# PLC_V1_0.net
KiCad netlist of a schematic drawn in Altium Designer
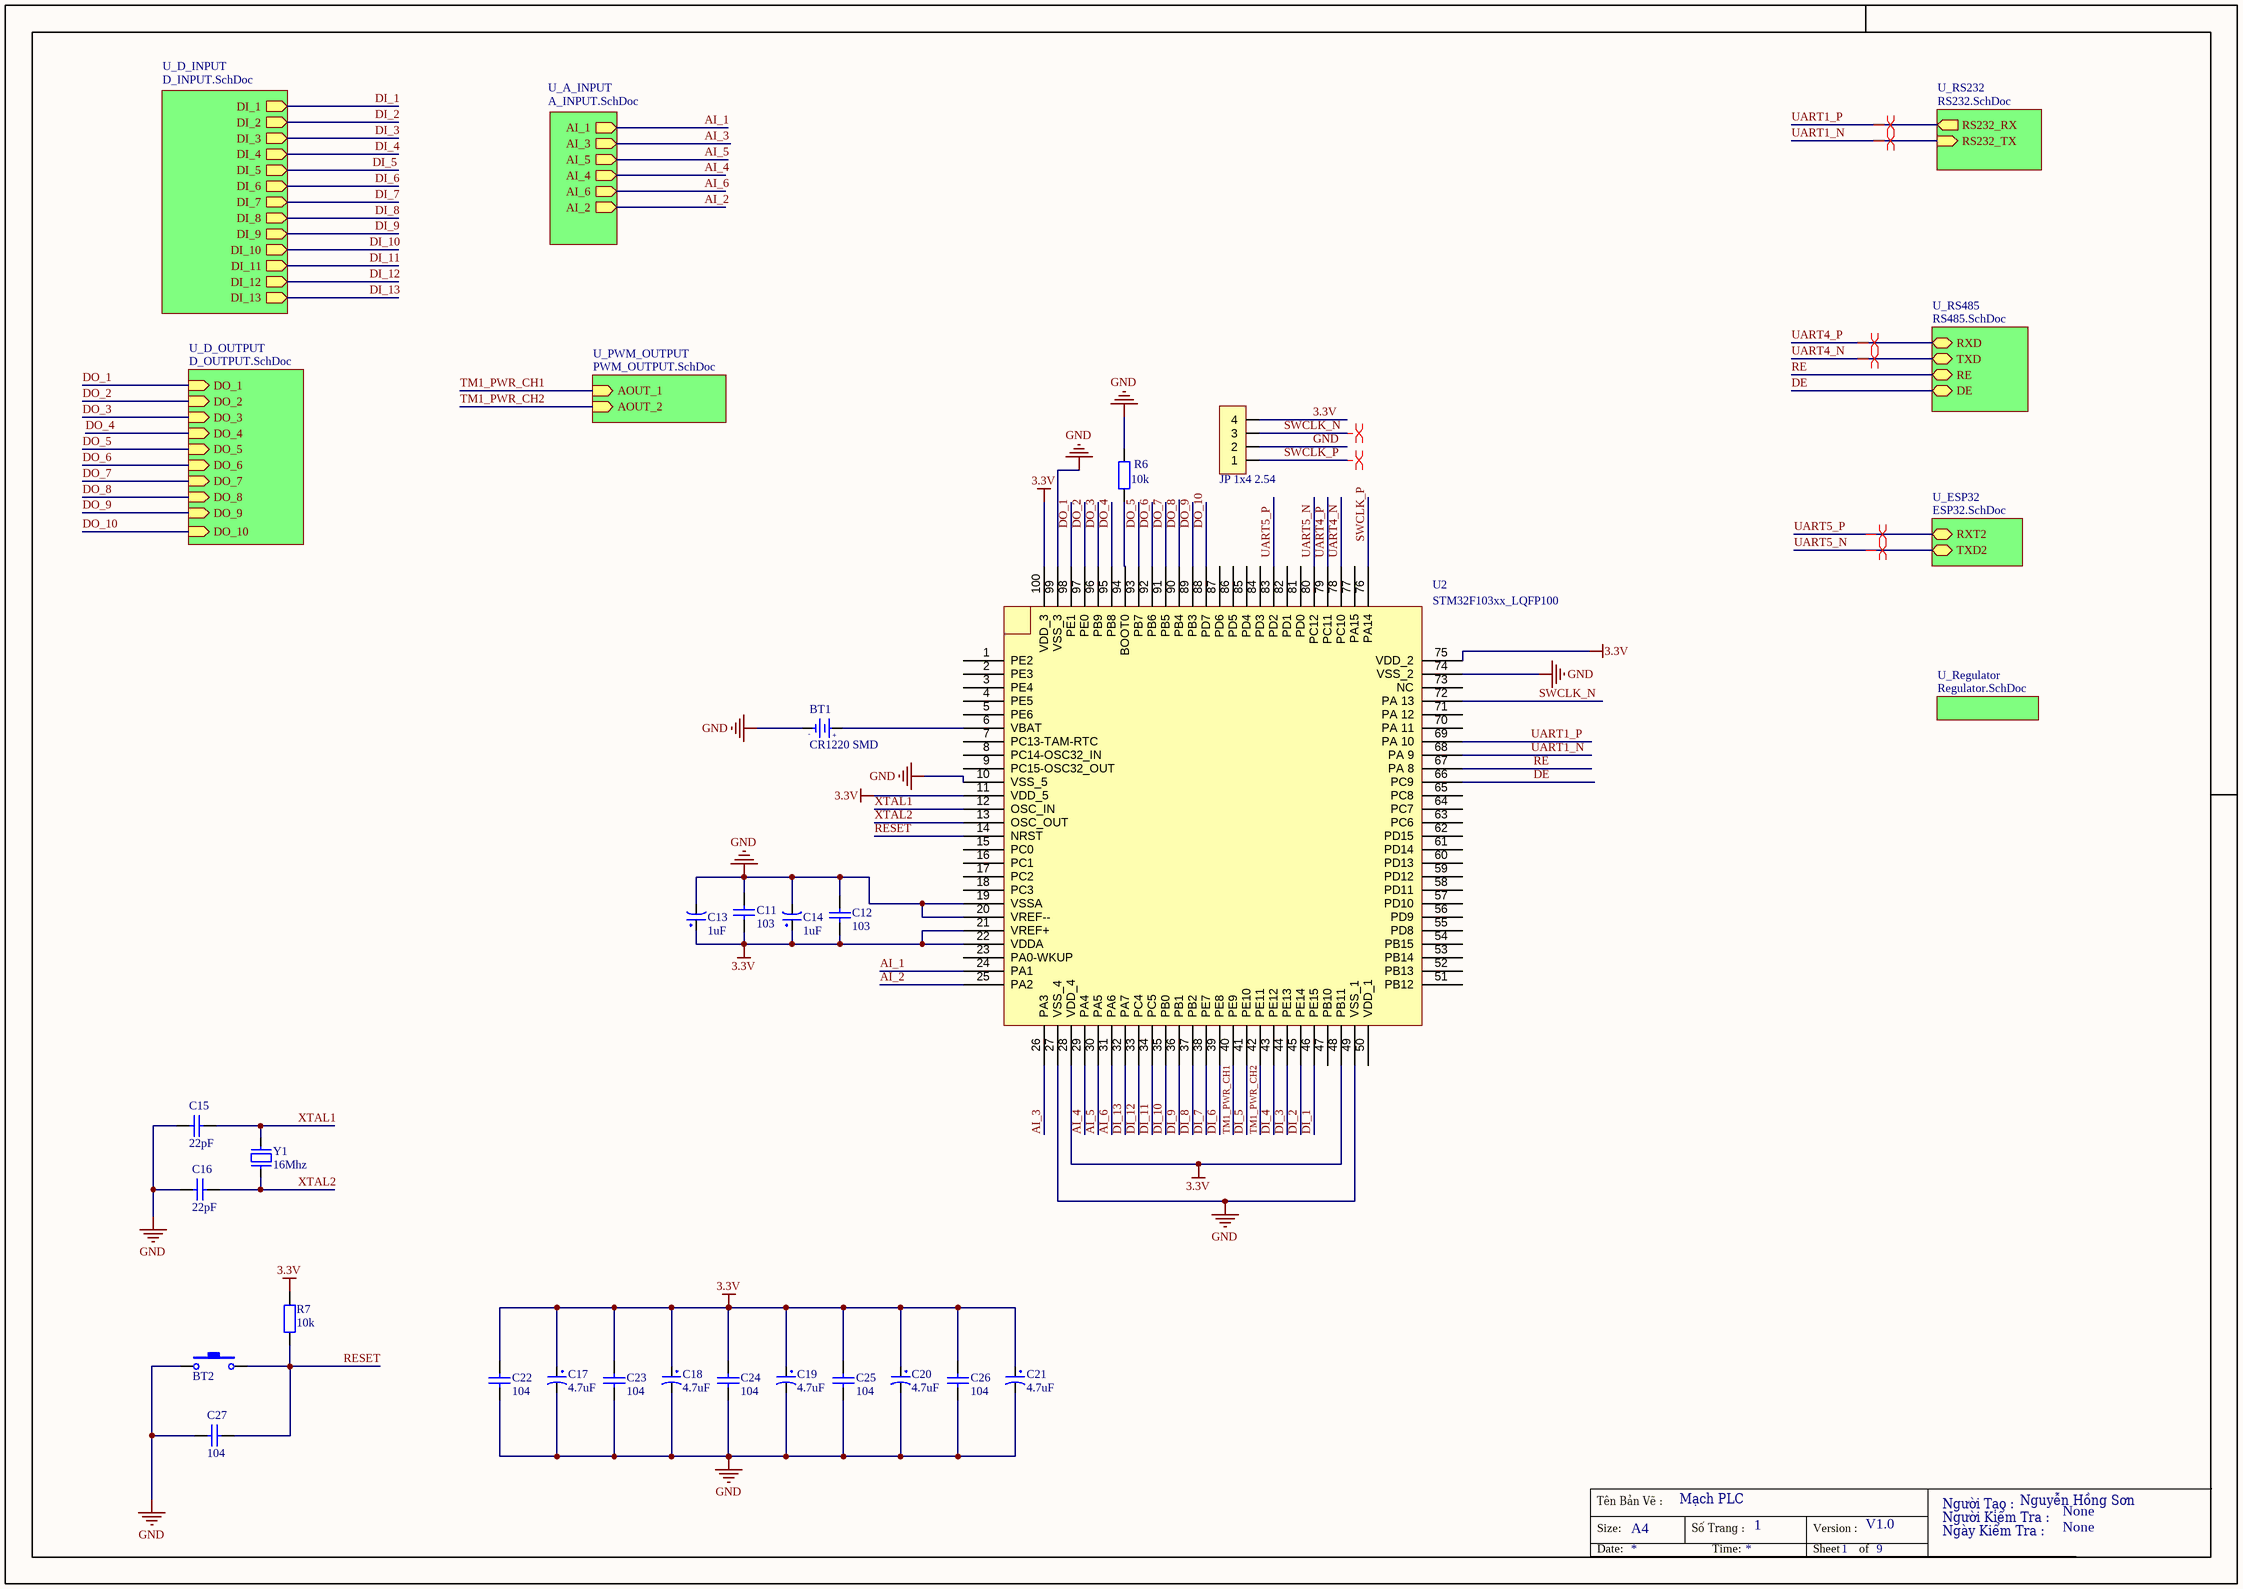
[diagram p0: PLC_V1.0.SchDoc]

(export (version "E")
  (design (tool "Eeschema 10.0.6"))
  (components
    (comp (ref "BT1")
      (value "CR1220 SMD")
      (footprint "DE PIN CR1220")
      (libsource (lib "Altium_Lib_by_KhueNguyenCreator") (part "De pin CR1220 SMD"))
    )
    (comp (ref "BT2")
      (value "Nut Nhan 2 Chan SMD 3x6x2.5")
      (footprint "Nut Nhan 2 Chan SMD 3x6x2.5")
      (libsource (lib "Altium_Lib_by_KhueNguyenCreator") (part "Nut Nhan 2 Chan SMD 3x6x2.5"))
    )
    (comp (ref "C11")
      (value "103")
      (footprint "tu 0603")
      (description "Dán")
      (libsource (lib "Altium_Lib_by_KhueNguyenCreator") (part "Tu 0603 103 50V 10%"))
    )
    (comp (ref "C12")
      (value "103")
      (footprint "tu 0603")
      (description "Dán")
      (libsource (lib "Altium_Lib_by_KhueNguyenCreator") (part "Tu 0603 103 50V 10%"))
    )
    (comp (ref "C13")
      (value "1uF")
      (footprint "tu tantalum smd3216")
      (description "Dán")
      (libsource (lib "Altium_Lib_by_KhueNguyenCreator") (part "Tu tantalum 1uF 25V SMD3216"))
    )
    (comp (ref "C14")
      (value "1uF")
      (footprint "tu tantalum smd3216")
      (description "Dán")
      (libsource (lib "Altium_Lib_by_KhueNguyenCreator") (part "Tu tantalum 1uF 25V SMD3216"))
    )
    (comp (ref "C15")
      (value "22pF")
      (footprint "tu 0805")
      (description "Dán")
      (libsource (lib "Altium_Lib_by_KhueNguyenCreator") (part "Tu 0805 22pF 50V 10%"))
    )
    (comp (ref "C16")
      (value "22pF")
      (footprint "tu 0805")
      (description "Dán")
      (libsource (lib "Altium_Lib_by_KhueNguyenCreator") (part "Tu 0805 22pF 50V 10%"))
    )
    (comp (ref "C17")
      (value "4.7uF")
      (footprint "tu tantalum smd6032")
      (description "Dán")
      (libsource (lib "Altium_Lib_by_KhueNguyenCreator") (part "Tu tantalum 4.7uF 35V SMD6032"))
    )
    (comp (ref "C18")
      (value "4.7uF")
      (footprint "tu tantalum smd6032")
      (description "Dán")
      (libsource (lib "Altium_Lib_by_KhueNguyenCreator") (part "Tu tantalum 4.7uF 35V SMD6032"))
    )
    (comp (ref "C19")
      (value "4.7uF")
      (footprint "tu tantalum smd6032")
      (description "Dán")
      (libsource (lib "Altium_Lib_by_KhueNguyenCreator") (part "Tu tantalum 4.7uF 35V SMD6032"))
    )
    (comp (ref "C20")
      (value "4.7uF")
      (footprint "tu tantalum smd6032")
      (description "Dán")
      (libsource (lib "Altium_Lib_by_KhueNguyenCreator") (part "Tu tantalum 4.7uF 35V SMD6032"))
    )
    (comp (ref "C21")
      (value "4.7uF")
      (footprint "tu tantalum smd6032")
      (description "Dán")
      (libsource (lib "Altium_Lib_by_KhueNguyenCreator") (part "Tu tantalum 4.7uF 35V SMD6032"))
    )
    (comp (ref "C22")
      (value "104")
      (footprint "tu 0805")
      (description "Dán 100nF")
      (libsource (lib "Altium_Lib_by_KhueNguyenCreator") (part "Tu 0805 104 50V 10%"))
    )
    (comp (ref "C23")
      (value "104")
      (footprint "tu 0805")
      (description "Dán 100nF")
      (libsource (lib "Altium_Lib_by_KhueNguyenCreator") (part "Tu 0805 104 50V 10%"))
    )
    (comp (ref "C24")
      (value "104")
      (footprint "tu 0805")
      (description "Dán 100nF")
      (libsource (lib "Altium_Lib_by_KhueNguyenCreator") (part "Tu 0805 104 50V 10%"))
    )
    (comp (ref "C25")
      (value "104")
      (footprint "tu 0805")
      (description "Dán 100nF")
      (libsource (lib "Altium_Lib_by_KhueNguyenCreator") (part "Tu 0805 104 50V 10%"))
    )
    (comp (ref "C26")
      (value "104")
      (footprint "tu 0805")
      (description "Dán 100nF")
      (libsource (lib "Altium_Lib_by_KhueNguyenCreator") (part "Tu 0805 104 50V 10%"))
    )
    (comp (ref "C27")
      (value "104")
      (footprint "tu 0805")
      (description "Dán")
      (libsource (lib "Altium_Lib_by_KhueNguyenCreator") (part "Tu 0805 104 50V 10%"))
    )
    (comp (ref "JP1")
      (value "JP 1x4 2.54")
      (footprint "JP 1x4 DT")
      (description "Cắm")
      (libsource (lib "Altium_Lib_by_KhueNguyenCreator") (part "JP 1x4 2.54 Duc Thang"))
    )
    (comp (ref "R6")
      (value "10k")
      (footprint "tro smd 0805")
      (description "Dán")
      (libsource (lib "Altium_Lib_by_KhueNguyenCreator") (part "Tro 0805 5% 10k"))
    )
    (comp (ref "R7")
      (value "10k")
      (footprint "tro smd 0805")
      (description "Dán")
      (libsource (lib "Altium_Lib_by_KhueNguyenCreator") (part "Tro 0805 5% 10k"))
    )
    (comp (ref "U2")
      (value "STM32F103xx_LQFP100")
      (footprint "STM32_LQFP100")
      (libsource (lib "Altium_Lib_by_KhueNguyenCreator") (part "STM32F103xx_LQFP100"))
    )
    (comp (ref "Y1")
      (value "16Mhz")
      (footprint "Thach Anh 2 chan SMD")
      (description "Crystal For all Crystal 2pin.")
      (libsource (lib "Altium_Lib_by_KhueNguyenCreator") (part "Thach Anh 2 chan SMD"))
    )
  )
  (nets
    (net (code "1") (name "/AI_1") (class "Default")
      (node (ref "U2") (pin "24") (pinfunction "PA1_24") (pintype "passive"))
    )
    (net (code "2") (name "/AI_2") (class "Default")
      (node (ref "U2") (pin "25") (pinfunction "PA2_25") (pintype "passive"))
    )
    (net (code "3") (name "/AI_3") (class "Default")
      (node (ref "U2") (pin "26") (pinfunction "PA3_26") (pintype "passive"))
    )
    (net (code "4") (name "/AI_4") (class "Default")
      (node (ref "U2") (pin "29") (pinfunction "PA4_29") (pintype "passive"))
    )
    (net (code "5") (name "/AI_5") (class "Default")
      (node (ref "U2") (pin "30") (pinfunction "PA5_30") (pintype "passive"))
    )
    (net (code "6") (name "/AI_6") (class "Default")
      (node (ref "U2") (pin "31") (pinfunction "PA6_31") (pintype "passive"))
    )
    (net (code "7") (name "/DE") (class "Default")
      (node (ref "U2") (pin "66") (pinfunction "PC9_66") (pintype "passive"))
    )
    (net (code "8") (name "/DI_1") (class "Default")
      (node (ref "U2") (pin "46") (pinfunction "PE15_46") (pintype "passive"))
    )
    (net (code "9") (name "/DI_2") (class "Default")
      (node (ref "U2") (pin "45") (pinfunction "PE14_45") (pintype "passive"))
    )
    (net (code "10") (name "/DI_3") (class "Default")
      (node (ref "U2") (pin "44") (pinfunction "PE13_44") (pintype "passive"))
    )
    (net (code "11") (name "/DI_4") (class "Default")
      (node (ref "U2") (pin "43") (pinfunction "PE12_43") (pintype "passive"))
    )
    (net (code "12") (name "/DI_5") (class "Default")
      (node (ref "U2") (pin "41") (pinfunction "PE10_41") (pintype "passive"))
    )
    (net (code "13") (name "/DI_6") (class "Default")
      (node (ref "U2") (pin "39") (pinfunction "PE8_39") (pintype "passive"))
    )
    (net (code "14") (name "/DI_7") (class "Default")
      (node (ref "U2") (pin "38") (pinfunction "PE7_38") (pintype "passive"))
    )
    (net (code "15") (name "/DI_8") (class "Default")
      (node (ref "U2") (pin "37") (pinfunction "PB2_37") (pintype "passive"))
    )
    (net (code "16") (name "/DI_9") (class "Default")
      (node (ref "U2") (pin "36") (pinfunction "PB1_36") (pintype "passive"))
    )
    (net (code "17") (name "/DI_10") (class "Default")
      (node (ref "U2") (pin "35") (pinfunction "PB0_35") (pintype "passive"))
    )
    (net (code "18") (name "/DI_11") (class "Default")
      (node (ref "U2") (pin "34") (pinfunction "PC5_34") (pintype "passive"))
    )
    (net (code "20") (name "/DI_12") (class "Default")
      (node (ref "U2") (pin "33") (pinfunction "PC4_33") (pintype "passive"))
    )
    (net (code "22") (name "/DI_13") (class "Default")
      (node (ref "U2") (pin "32") (pinfunction "PA7_32") (pintype "passive"))
    )
    (net (code "24") (name "/DO_1") (class "Default")
      (node (ref "U2") (pin "98") (pinfunction "PE1_98") (pintype "passive"))
    )
    (net (code "25") (name "/DO_2") (class "Default")
      (node (ref "U2") (pin "97") (pinfunction "PE0_97") (pintype "passive"))
    )
    (net (code "26") (name "/DO_3") (class "Default")
      (node (ref "U2") (pin "96") (pinfunction "PB9_96") (pintype "passive"))
    )
    (net (code "27") (name "/DO_4") (class "Default")
      (node (ref "U2") (pin "95") (pinfunction "PB8_95") (pintype "passive"))
    )
    (net (code "28") (name "/DO_5") (class "Default")
      (node (ref "U2") (pin "93") (pinfunction "PB7_93") (pintype "passive"))
    )
    (net (code "29") (name "/DO_6") (class "Default")
      (node (ref "U2") (pin "92") (pinfunction "PB6_92") (pintype "passive"))
    )
    (net (code "30") (name "/DO_7") (class "Default")
      (node (ref "U2") (pin "91") (pinfunction "PB5_91") (pintype "passive"))
    )
    (net (code "31") (name "/DO_8") (class "Default")
      (node (ref "U2") (pin "90") (pinfunction "PB4_90") (pintype "passive"))
    )
    (net (code "32") (name "/DO_9") (class "Default")
      (node (ref "U2") (pin "89") (pinfunction "PB3_89") (pintype "passive"))
    )
    (net (code "33") (name "/DO_10") (class "Default")
      (node (ref "U2") (pin "88") (pinfunction "PD7_88") (pintype "passive"))
    )
    (net (code "34") (name "/RE") (class "Default")
      (node (ref "U2") (pin "67") (pinfunction "PA_8_67") (pintype "passive"))
    )
    (net (code "35") (name "/RESET") (class "Default")
      (node (ref "BT2") (pin "2") (pinfunction "2_2") (pintype "passive"))
      (node (ref "C27") (pin "1") (pinfunction "1_1") (pintype "passive"))
      (node (ref "R7") (pin "2") (pinfunction "2_2") (pintype "passive"))
      (node (ref "U2") (pin "14") (pinfunction "NRST_14") (pintype "passive"))
    )
    (net (code "36") (name "/SWCLK_N") (class "Default")
      (node (ref "JP1") (pin "3") (pinfunction "3_3") (pintype "passive"))
      (node (ref "U2") (pin "72") (pinfunction "PA_13_72") (pintype "passive"))
    )
    (net (code "37") (name "/SWCLK_P") (class "Default")
      (node (ref "JP1") (pin "1") (pinfunction "1_1") (pintype "passive"))
      (node (ref "U2") (pin "76") (pinfunction "PA14_76") (pintype "passive"))
    )
    (net (code "38") (name "/TM1_PWR_CH1") (class "Default")
      (node (ref "U2") (pin "40") (pinfunction "PE9_40") (pintype "passive"))
    )
    (net (code "39") (name "/TM1_PWR_CH2") (class "Default")
      (node (ref "U2") (pin "42") (pinfunction "PE11_42") (pintype "passive"))
    )
    (net (code "40") (name "/UART1_N") (class "Default")
      (node (ref "U2") (pin "68") (pinfunction "PA_9_68") (pintype "passive"))
    )
    (net (code "41") (name "/UART1_P") (class "Default")
      (node (ref "U2") (pin "69") (pinfunction "PA_10_69") (pintype "passive"))
    )
    (net (code "42") (name "/UART4_N") (class "Default")
      (node (ref "U2") (pin "78") (pinfunction "PC10_78") (pintype "passive"))
    )
    (net (code "43") (name "/UART4_P") (class "Default")
      (node (ref "U2") (pin "79") (pinfunction "PC11_79") (pintype "passive"))
    )
    (net (code "44") (name "/UART5_N") (class "Default")
      (node (ref "U2") (pin "80") (pinfunction "PC12_80") (pintype "passive"))
    )
    (net (code "45") (name "/UART5_P") (class "Default")
      (node (ref "U2") (pin "83") (pinfunction "PD2_83") (pintype "passive"))
    )
    (net (code "46") (name "/XTAL1") (class "Default")
      (node (ref "C15") (pin "1") (pinfunction "1_1") (pintype "passive"))
      (node (ref "U2") (pin "12") (pinfunction "OSC_IN_12") (pintype "passive"))
      (node (ref "Y1") (pin "2") (pinfunction "2_2") (pintype "passive"))
    )
    (net (code "47") (name "/XTAL2") (class "Default")
      (node (ref "C16") (pin "1") (pinfunction "1_1") (pintype "passive"))
      (node (ref "U2") (pin "13") (pinfunction "OSC_OUT_13") (pintype "passive"))
      (node (ref "Y1") (pin "1") (pinfunction "1_1") (pintype "passive"))
    )
    (net (code "48") (name "3.3V") (class "Default")
      (node (ref "C11") (pin "1") (pinfunction "1_1") (pintype "passive"))
      (node (ref "C12") (pin "1") (pinfunction "1_1") (pintype "passive"))
      (node (ref "C13") (pin "1") (pinfunction "1_1") (pintype "passive"))
      (node (ref "C14") (pin "1") (pinfunction "1_1") (pintype "passive"))
      (node (ref "C17") (pin "1") (pinfunction "1_1") (pintype "passive"))
      (node (ref "C18") (pin "1") (pinfunction "1_1") (pintype "passive"))
      (node (ref "C19") (pin "1") (pinfunction "1_1") (pintype "passive"))
      (node (ref "C20") (pin "1") (pinfunction "1_1") (pintype "passive"))
      (node (ref "C21") (pin "1") (pinfunction "1_1") (pintype "passive"))
      (node (ref "C22") (pin "2") (pinfunction "2_2") (pintype "passive"))
      (node (ref "C23") (pin "2") (pinfunction "2_2") (pintype "passive"))
      (node (ref "C24") (pin "2") (pinfunction "2_2") (pintype "passive"))
      (node (ref "C25") (pin "2") (pinfunction "2_2") (pintype "passive"))
      (node (ref "C26") (pin "2") (pinfunction "2_2") (pintype "passive"))
      (node (ref "JP1") (pin "4") (pinfunction "4_4") (pintype "passive"))
      (node (ref "R7") (pin "1") (pinfunction "1_1") (pintype "passive"))
      (node (ref "U2") (pin "100") (pinfunction "VDD_3_100") (pintype "passive"))
      (node (ref "U2") (pin "11") (pinfunction "VDD_5_11") (pintype "passive"))
      (node (ref "U2") (pin "21") (pinfunction "VREF+_21") (pintype "passive"))
      (node (ref "U2") (pin "22") (pinfunction "VDDA_22") (pintype "passive"))
      (node (ref "U2") (pin "28") (pinfunction "VDD_4_28") (pintype "passive"))
      (node (ref "U2") (pin "48") (pinfunction "PB11_48") (pintype "passive"))
      (node (ref "U2") (pin "75") (pinfunction "VDD_2_75") (pintype "passive"))
    )
    (net (code "49") (name "GND") (class "Default")
      (node (ref "BT1") (pin "2") (pinfunction "GND_2") (pintype "passive"))
      (node (ref "BT2") (pin "1") (pinfunction "1_1") (pintype "passive"))
      (node (ref "C11") (pin "2") (pinfunction "2_2") (pintype "passive"))
      (node (ref "C12") (pin "2") (pinfunction "2_2") (pintype "passive"))
      (node (ref "C13") (pin "2") (pinfunction "2_2") (pintype "passive"))
      (node (ref "C14") (pin "2") (pinfunction "2_2") (pintype "passive"))
      (node (ref "C15") (pin "2") (pinfunction "2_2") (pintype "passive"))
      (node (ref "C16") (pin "2") (pinfunction "2_2") (pintype "passive"))
      (node (ref "C17") (pin "2") (pinfunction "2_2") (pintype "passive"))
      (node (ref "C18") (pin "2") (pinfunction "2_2") (pintype "passive"))
      (node (ref "C19") (pin "2") (pinfunction "2_2") (pintype "passive"))
      (node (ref "C20") (pin "2") (pinfunction "2_2") (pintype "passive"))
      (node (ref "C21") (pin "2") (pinfunction "2_2") (pintype "passive"))
      (node (ref "C22") (pin "1") (pinfunction "1_1") (pintype "passive"))
      (node (ref "C23") (pin "1") (pinfunction "1_1") (pintype "passive"))
      (node (ref "C24") (pin "1") (pinfunction "1_1") (pintype "passive"))
      (node (ref "C25") (pin "1") (pinfunction "1_1") (pintype "passive"))
      (node (ref "C26") (pin "1") (pinfunction "1_1") (pintype "passive"))
      (node (ref "C27") (pin "2") (pinfunction "2_2") (pintype "passive"))
      (node (ref "JP1") (pin "2") (pinfunction "2_2") (pintype "passive"))
      (node (ref "R6") (pin "2") (pinfunction "2_2") (pintype "passive"))
      (node (ref "U2") (pin "10") (pinfunction "VSS_5_10") (pintype "passive"))
      (node (ref "U2") (pin "19") (pinfunction "VSSA_19") (pintype "passive"))
      (node (ref "U2") (pin "20") (pinfunction "VREF--_20") (pintype "passive"))
      (node (ref "U2") (pin "27") (pinfunction "VSS_4_27") (pintype "passive"))
      (node (ref "U2") (pin "49") (pinfunction "VSS_1_49") (pintype "passive"))
      (node (ref "U2") (pin "74") (pinfunction "VSS_2_74") (pintype "passive"))
      (node (ref "U2") (pin "99") (pinfunction "VSS_3_99") (pintype "passive"))
    )
    (net (code "50") (name "Net-(BT1-+3V)") (class "Default")
      (node (ref "BT1") (pin "1") (pinfunction "+3V_1") (pintype "passive"))
      (node (ref "U2") (pin "6") (pinfunction "VBAT_6") (pintype "passive"))
    )
    (net (code "51") (name "Net-(U2-BOOT0)") (class "Default")
      (node (ref "R6") (pin "1") (pinfunction "1_1") (pintype "passive"))
      (node (ref "U2") (pin "94") (pinfunction "BOOT0_94") (pintype "passive"))
    )
    (net (code "52") (name "unconnected-(U2-NC-Pad73)") (class "Default")
      (node (ref "U2") (pin "73") (pinfunction "NC_73") (pintype "passive"))
    )
    (net (code "53") (name "unconnected-(U2-PA0-WKUP-Pad23)") (class "Default")
      (node (ref "U2") (pin "23") (pinfunction "PA0-WKUP_23") (pintype "passive"))
    )
    (net (code "54") (name "unconnected-(U2-PA15-Pad77)") (class "Default")
      (node (ref "U2") (pin "77") (pinfunction "PA15_77") (pintype "passive"))
    )
    (net (code "55") (name "unconnected-(U2-PA_11-Pad70)") (class "Default")
      (node (ref "U2") (pin "70") (pinfunction "PA_11_70") (pintype "passive"))
    )
    (net (code "56") (name "unconnected-(U2-PA_12-Pad71)") (class "Default")
      (node (ref "U2") (pin "71") (pinfunction "PA_12_71") (pintype "passive"))
    )
    (net (code "57") (name "unconnected-(U2-PB10-Pad47)") (class "Default")
      (node (ref "U2") (pin "47") (pinfunction "PB10_47") (pintype "passive"))
    )
    (net (code "58") (name "unconnected-(U2-PB12-Pad51)") (class "Default")
      (node (ref "U2") (pin "51") (pinfunction "PB12_51") (pintype "passive"))
    )
    (net (code "59") (name "unconnected-(U2-PB13-Pad52)") (class "Default")
      (node (ref "U2") (pin "52") (pinfunction "PB13_52") (pintype "passive"))
    )
    (net (code "60") (name "unconnected-(U2-PB14-Pad53)") (class "Default")
      (node (ref "U2") (pin "53") (pinfunction "PB14_53") (pintype "passive"))
    )
    (net (code "61") (name "unconnected-(U2-PB15-Pad54)") (class "Default")
      (node (ref "U2") (pin "54") (pinfunction "PB15_54") (pintype "passive"))
    )
    (net (code "62") (name "unconnected-(U2-PC0-Pad15)") (class "Default")
      (node (ref "U2") (pin "15") (pinfunction "PC0_15") (pintype "passive"))
    )
    (net (code "63") (name "unconnected-(U2-PC1-Pad16)") (class "Default")
      (node (ref "U2") (pin "16") (pinfunction "PC1_16") (pintype "passive"))
    )
    (net (code "64") (name "unconnected-(U2-PC2-Pad17)") (class "Default")
      (node (ref "U2") (pin "17") (pinfunction "PC2_17") (pintype "passive"))
    )
    (net (code "65") (name "unconnected-(U2-PC3-Pad18)") (class "Default")
      (node (ref "U2") (pin "18") (pinfunction "PC3_18") (pintype "passive"))
    )
    (net (code "66") (name "unconnected-(U2-PC6-Pad63)") (class "Default")
      (node (ref "U2") (pin "63") (pinfunction "PC6_63") (pintype "passive"))
    )
    (net (code "67") (name "unconnected-(U2-PC7-Pad64)") (class "Default")
      (node (ref "U2") (pin "64") (pinfunction "PC7_64") (pintype "passive"))
    )
    (net (code "68") (name "unconnected-(U2-PC8-Pad65)") (class "Default")
      (node (ref "U2") (pin "65") (pinfunction "PC8_65") (pintype "passive"))
    )
    (net (code "69") (name "unconnected-(U2-PC13-TAM-RTC-Pad7)") (class "Default")
      (node (ref "U2") (pin "7") (pinfunction "PC13-TAM-RTC_7") (pintype "passive"))
    )
    (net (code "70") (name "unconnected-(U2-PC14-OSC32_IN-Pad8)") (class "Default")
      (node (ref "U2") (pin "8") (pinfunction "PC14-OSC32_IN_8") (pintype "passive"))
    )
    (net (code "71") (name "unconnected-(U2-PC15-OSC32_OUT-Pad9)") (class "Default")
      (node (ref "U2") (pin "9") (pinfunction "PC15-OSC32_OUT_9") (pintype "passive"))
    )
    (net (code "72") (name "unconnected-(U2-PD0-Pad81)") (class "Default")
      (node (ref "U2") (pin "81") (pinfunction "PD0_81") (pintype "passive"))
    )
    (net (code "73") (name "unconnected-(U2-PD1-Pad82)") (class "Default")
      (node (ref "U2") (pin "82") (pinfunction "PD1_82") (pintype "passive"))
    )
    (net (code "74") (name "unconnected-(U2-PD3-Pad84)") (class "Default")
      (node (ref "U2") (pin "84") (pinfunction "PD3_84") (pintype "passive"))
    )
    (net (code "75") (name "unconnected-(U2-PD4-Pad85)") (class "Default")
      (node (ref "U2") (pin "85") (pinfunction "PD4_85") (pintype "passive"))
    )
    (net (code "76") (name "unconnected-(U2-PD5-Pad86)") (class "Default")
      (node (ref "U2") (pin "86") (pinfunction "PD5_86") (pintype "passive"))
    )
    (net (code "77") (name "unconnected-(U2-PD6-Pad87)") (class "Default")
      (node (ref "U2") (pin "87") (pinfunction "PD6_87") (pintype "passive"))
    )
    (net (code "78") (name "unconnected-(U2-PD8-Pad55)") (class "Default")
      (node (ref "U2") (pin "55") (pinfunction "PD8_55") (pintype "passive"))
    )
    (net (code "79") (name "unconnected-(U2-PD9-Pad56)") (class "Default")
      (node (ref "U2") (pin "56") (pinfunction "PD9_56") (pintype "passive"))
    )
    (net (code "80") (name "unconnected-(U2-PD10-Pad57)") (class "Default")
      (node (ref "U2") (pin "57") (pinfunction "PD10_57") (pintype "passive"))
    )
    (net (code "81") (name "unconnected-(U2-PD11-Pad58)") (class "Default")
      (node (ref "U2") (pin "58") (pinfunction "PD11_58") (pintype "passive"))
    )
    (net (code "82") (name "unconnected-(U2-PD12-Pad59)") (class "Default")
      (node (ref "U2") (pin "59") (pinfunction "PD12_59") (pintype "passive"))
    )
    (net (code "83") (name "unconnected-(U2-PD13-Pad60)") (class "Default")
      (node (ref "U2") (pin "60") (pinfunction "PD13_60") (pintype "passive"))
    )
    (net (code "84") (name "unconnected-(U2-PD14-Pad61)") (class "Default")
      (node (ref "U2") (pin "61") (pinfunction "PD14_61") (pintype "passive"))
    )
    (net (code "85") (name "unconnected-(U2-PD15-Pad62)") (class "Default")
      (node (ref "U2") (pin "62") (pinfunction "PD15_62") (pintype "passive"))
    )
    (net (code "86") (name "unconnected-(U2-PE2-Pad1)") (class "Default")
      (node (ref "U2") (pin "1") (pinfunction "PE2_1") (pintype "passive"))
    )
    (net (code "87") (name "unconnected-(U2-PE3-Pad2)") (class "Default")
      (node (ref "U2") (pin "2") (pinfunction "PE3_2") (pintype "passive"))
    )
    (net (code "88") (name "unconnected-(U2-PE4-Pad3)") (class "Default")
      (node (ref "U2") (pin "3") (pinfunction "PE4_3") (pintype "passive"))
    )
    (net (code "89") (name "unconnected-(U2-PE5-Pad4)") (class "Default")
      (node (ref "U2") (pin "4") (pinfunction "PE5_4") (pintype "passive"))
    )
    (net (code "90") (name "unconnected-(U2-PE6-Pad5)") (class "Default")
      (node (ref "U2") (pin "5") (pinfunction "PE6_5") (pintype "passive"))
    )
    (net (code "91") (name "unconnected-(U2-VDD_1-Pad50)") (class "Default")
      (node (ref "U2") (pin "50") (pinfunction "VDD_1_50") (pintype "passive"))
    )
  )
)
